# LCDTFT_FPC30P_LVDS_SCT070013.net
KiCad netlist of a schematic drawn in Altium Designer
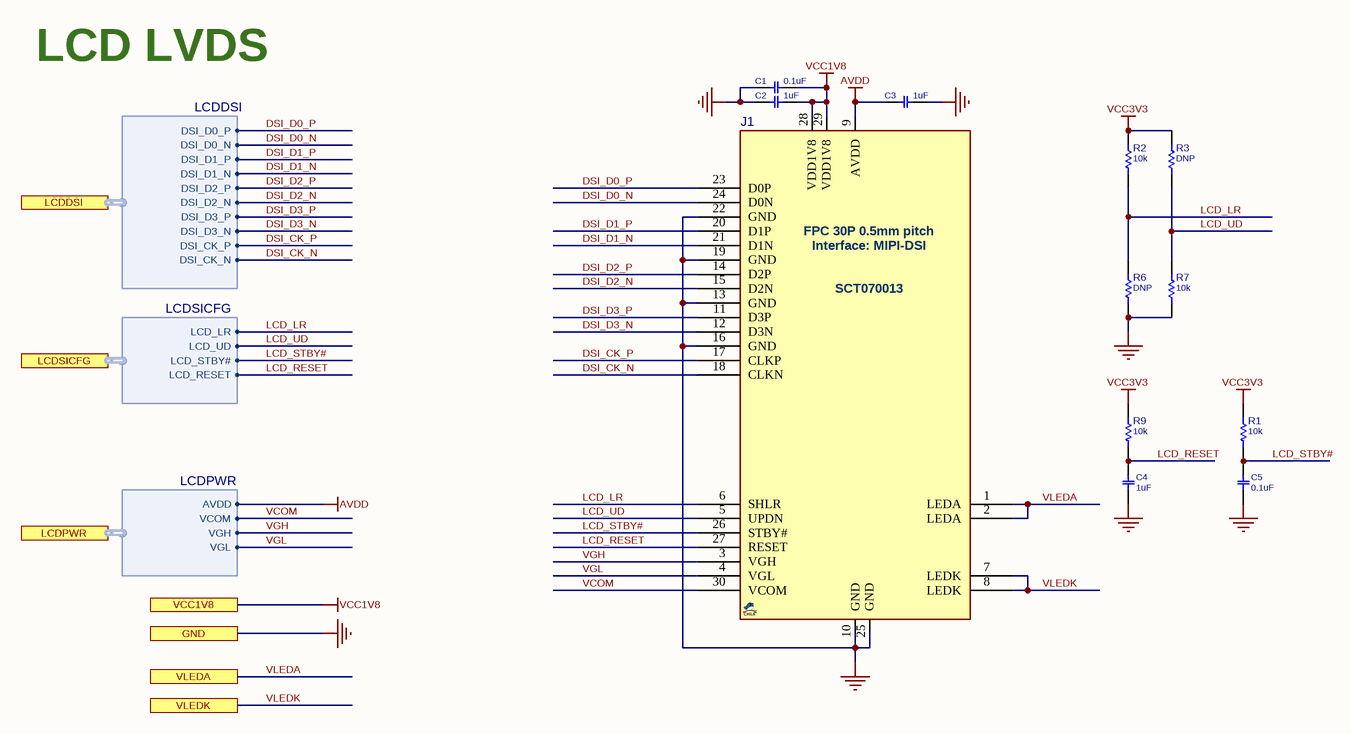
[diagram p0: LCDTFT_FPC30P_LVDS_SCT070013.SchDoc]

(export (version "E")
  (design (tool "Eeschema 10.0.6"))
  (components
    (comp (ref "C1")
      (value "0.1uF")
      (footprint "C0402")
      (description "CAP, MLCC")
      (fields (field (name "MANF_P#") "GRM155R71H104KE14D") (field (name "MANF") "Murata"))
      (libsource (lib "passive_smd") (part "CAP_SMD_MLCC"))
    )
    (comp (ref "C2")
      (value "1uF")
      (footprint "C0402")
      (description "CAP, MLCC")
      (fields (field (name "MANF_P#") "CL05A105KO5NNND") (field (name "MANF") "Samsung"))
      (libsource (lib "passive_smd") (part "CAP_SMD_MLCC"))
    )
    (comp (ref "C3")
      (value "1uF")
      (footprint "C0402")
      (description "CAP, MLCC")
      (fields (field (name "MANF_P#") "CL05A105KO5NNND") (field (name "MANF") "Samsung"))
      (libsource (lib "passive_smd") (part "CAP_SMD_MLCC"))
    )
    (comp (ref "C4")
      (value "1uF")
      (footprint "C0402")
      (description "CAP, MLCC")
      (fields (field (name "MANF_P#") "CL05A105KO5NNND") (field (name "MANF") "Samsung"))
      (libsource (lib "passive_smd") (part "CAP_SMD_MLCC"))
    )
    (comp (ref "C5")
      (value "0.1uF")
      (footprint "C0402")
      (description "CAP, MLCC")
      (fields (field (name "MANF_P#") "GRM155R71H104KE14D") (field (name "MANF") "Murata"))
      (libsource (lib "passive_smd") (part "CAP_SMD_MLCC"))
    )
    (comp (ref "J1")
      (value "FPC_30_0.5mm")
      (footprint "FPC50_30")
      (description "LCD TFT Color, FPC30P, LVDS")
      (libsource (lib "lcdtft") (part "LCDTFT_DSI_FPC30P_SCT070013"))
    )
    (comp (ref "R1")
      (value "10k")
      (footprint "R0402")
      (description "RESISTOR, SMD")
      (libsource (lib "passive_res_smd") (part "RES_SMD"))
    )
    (comp (ref "R2")
      (value "10k")
      (footprint "R0402")
      (description "RESISTOR, SMD")
      (libsource (lib "passive_res_smd") (part "RES_SMD"))
    )
    (comp (ref "R3")
      (value "DNP")
      (footprint "R0402")
      (description "RESISTOR, SMD")
      (libsource (lib "passive_res_smd") (part "RES_SMD"))
    )
    (comp (ref "R6")
      (value "DNP")
      (footprint "R0402")
      (description "RESISTOR, SMD")
      (libsource (lib "passive_res_smd") (part "RES_SMD"))
    )
    (comp (ref "R7")
      (value "10k")
      (footprint "R0402")
      (description "RESISTOR, SMD")
      (libsource (lib "passive_res_smd") (part "RES_SMD"))
    )
    (comp (ref "R9")
      (value "10k")
      (footprint "R0402")
      (description "RESISTOR, SMD")
      (libsource (lib "passive_res_smd") (part "RES_SMD"))
    )
  )
  (nets
    (net (code "4") (name "/DSI_CK_N") (class "Default")
      (node (ref "J1") (pin "18") (pinfunction "CLKN_18") (pintype "passive"))
    )
    (net (code "5") (name "/DSI_CK_P") (class "Default")
      (node (ref "J1") (pin "17") (pinfunction "CLKP_17") (pintype "passive"))
    )
    (net (code "6") (name "/DSI_D0_N") (class "Default")
      (node (ref "J1") (pin "24") (pinfunction "D0N_24") (pintype "passive"))
    )
    (net (code "7") (name "/DSI_D0_P") (class "Default")
      (node (ref "J1") (pin "23") (pinfunction "D0P_23") (pintype "passive"))
    )
    (net (code "8") (name "/DSI_D1_N") (class "Default")
      (node (ref "J1") (pin "21") (pinfunction "D1N_21") (pintype "passive"))
    )
    (net (code "9") (name "/DSI_D1_P") (class "Default")
      (node (ref "J1") (pin "20") (pinfunction "D1P_20") (pintype "passive"))
    )
    (net (code "10") (name "/DSI_D2_N") (class "Default")
      (node (ref "J1") (pin "15") (pinfunction "D2N_15") (pintype "passive"))
    )
    (net (code "11") (name "/DSI_D2_P") (class "Default")
      (node (ref "J1") (pin "14") (pinfunction "D2P_14") (pintype "passive"))
    )
    (net (code "12") (name "/DSI_D3_N") (class "Default")
      (node (ref "J1") (pin "12") (pinfunction "D3N_12") (pintype "passive"))
    )
    (net (code "13") (name "/DSI_D3_P") (class "Default")
      (node (ref "J1") (pin "11") (pinfunction "D3P_11") (pintype "passive"))
    )
    (net (code "14") (name "/LCD_LR") (class "Default")
      (node (ref "J1") (pin "6") (pinfunction "SHLR_6") (pintype "passive"))
      (node (ref "R2") (pin "2") (pinfunction "2_2") (pintype "passive"))
      (node (ref "R6") (pin "1") (pinfunction "1_1") (pintype "passive"))
    )
    (net (code "15") (name "/LCD_RESET") (class "Default")
      (node (ref "C4") (pin "1") (pinfunction "1_1") (pintype "passive"))
      (node (ref "J1") (pin "27") (pinfunction "RESET_27") (pintype "passive"))
      (node (ref "R9") (pin "2") (pinfunction "2_2") (pintype "passive"))
    )
    (net (code "16") (name "/LCD_STBY#") (class "Default")
      (node (ref "C5") (pin "1") (pinfunction "1_1") (pintype "passive"))
      (node (ref "J1") (pin "26") (pinfunction "STBY#_26") (pintype "passive"))
      (node (ref "R1") (pin "2") (pinfunction "2_2") (pintype "passive"))
    )
    (net (code "17") (name "/LCD_UD") (class "Default")
      (node (ref "J1") (pin "5") (pinfunction "UPDN_5") (pintype "passive"))
      (node (ref "R3") (pin "2") (pinfunction "2_2") (pintype "passive"))
      (node (ref "R7") (pin "1") (pinfunction "1_1") (pintype "passive"))
    )
    (net (code "18") (name "/VCOM") (class "Default")
      (node (ref "J1") (pin "30") (pinfunction "VCOM_30") (pintype "passive"))
    )
    (net (code "19") (name "/VGH") (class "Default")
      (node (ref "J1") (pin "3") (pinfunction "VGH_3") (pintype "passive"))
    )
    (net (code "20") (name "/VGL") (class "Default")
      (node (ref "J1") (pin "4") (pinfunction "VGL_4") (pintype "passive"))
    )
    (net (code "21") (name "/VLEDA") (class "Default")
      (node (ref "J1") (pin "1") (pinfunction "LEDA_1") (pintype "passive"))
      (node (ref "J1") (pin "2") (pinfunction "LEDA_2") (pintype "passive"))
    )
    (net (code "22") (name "/VLEDK") (class "Default")
      (node (ref "J1") (pin "7") (pinfunction "LEDK_7") (pintype "passive"))
      (node (ref "J1") (pin "8") (pinfunction "LEDK_8") (pintype "passive"))
    )
    (net (code "26") (name "AVDD") (class "Default")
      (node (ref "C3") (pin "2") (pinfunction "2_2") (pintype "passive"))
      (node (ref "J1") (pin "9") (pinfunction "AVDD_9") (pintype "passive"))
    )
    (net (code "27") (name "GND") (class "Default")
      (node (ref "C1") (pin "2") (pinfunction "2_2") (pintype "passive"))
      (node (ref "C2") (pin "2") (pinfunction "2_2") (pintype "passive"))
      (node (ref "C3") (pin "1") (pinfunction "1_1") (pintype "passive"))
      (node (ref "C4") (pin "2") (pinfunction "2_2") (pintype "passive"))
      (node (ref "C5") (pin "2") (pinfunction "2_2") (pintype "passive"))
      (node (ref "J1") (pin "10") (pinfunction "GND_10") (pintype "passive"))
      (node (ref "J1") (pin "13") (pinfunction "GND_13") (pintype "passive"))
      (node (ref "J1") (pin "16") (pinfunction "GND_16") (pintype "passive"))
      (node (ref "J1") (pin "19") (pinfunction "GND_19") (pintype "passive"))
      (node (ref "J1") (pin "22") (pinfunction "GND_22") (pintype "passive"))
      (node (ref "J1") (pin "25") (pinfunction "GND_25") (pintype "passive"))
      (node (ref "R6") (pin "2") (pinfunction "2_2") (pintype "passive"))
      (node (ref "R7") (pin "2") (pinfunction "2_2") (pintype "passive"))
    )
    (net (code "28") (name "VCC1V8") (class "Default")
      (node (ref "C1") (pin "1") (pinfunction "1_1") (pintype "passive"))
      (node (ref "C2") (pin "1") (pinfunction "1_1") (pintype "passive"))
      (node (ref "J1") (pin "28") (pinfunction "VDD1V8_28") (pintype "passive"))
      (node (ref "J1") (pin "29") (pinfunction "VDD1V8_29") (pintype "passive"))
    )
    (net (code "29") (name "VCC3V3") (class "Default")
      (node (ref "R1") (pin "1") (pinfunction "1_1") (pintype "passive"))
      (node (ref "R2") (pin "1") (pinfunction "1_1") (pintype "passive"))
      (node (ref "R3") (pin "1") (pinfunction "1_1") (pintype "passive"))
      (node (ref "R9") (pin "1") (pinfunction "1_1") (pintype "passive"))
    )
  )
)
